# MODULO2_def.net
KiCad netlist of a schematic drawn in EAGLE
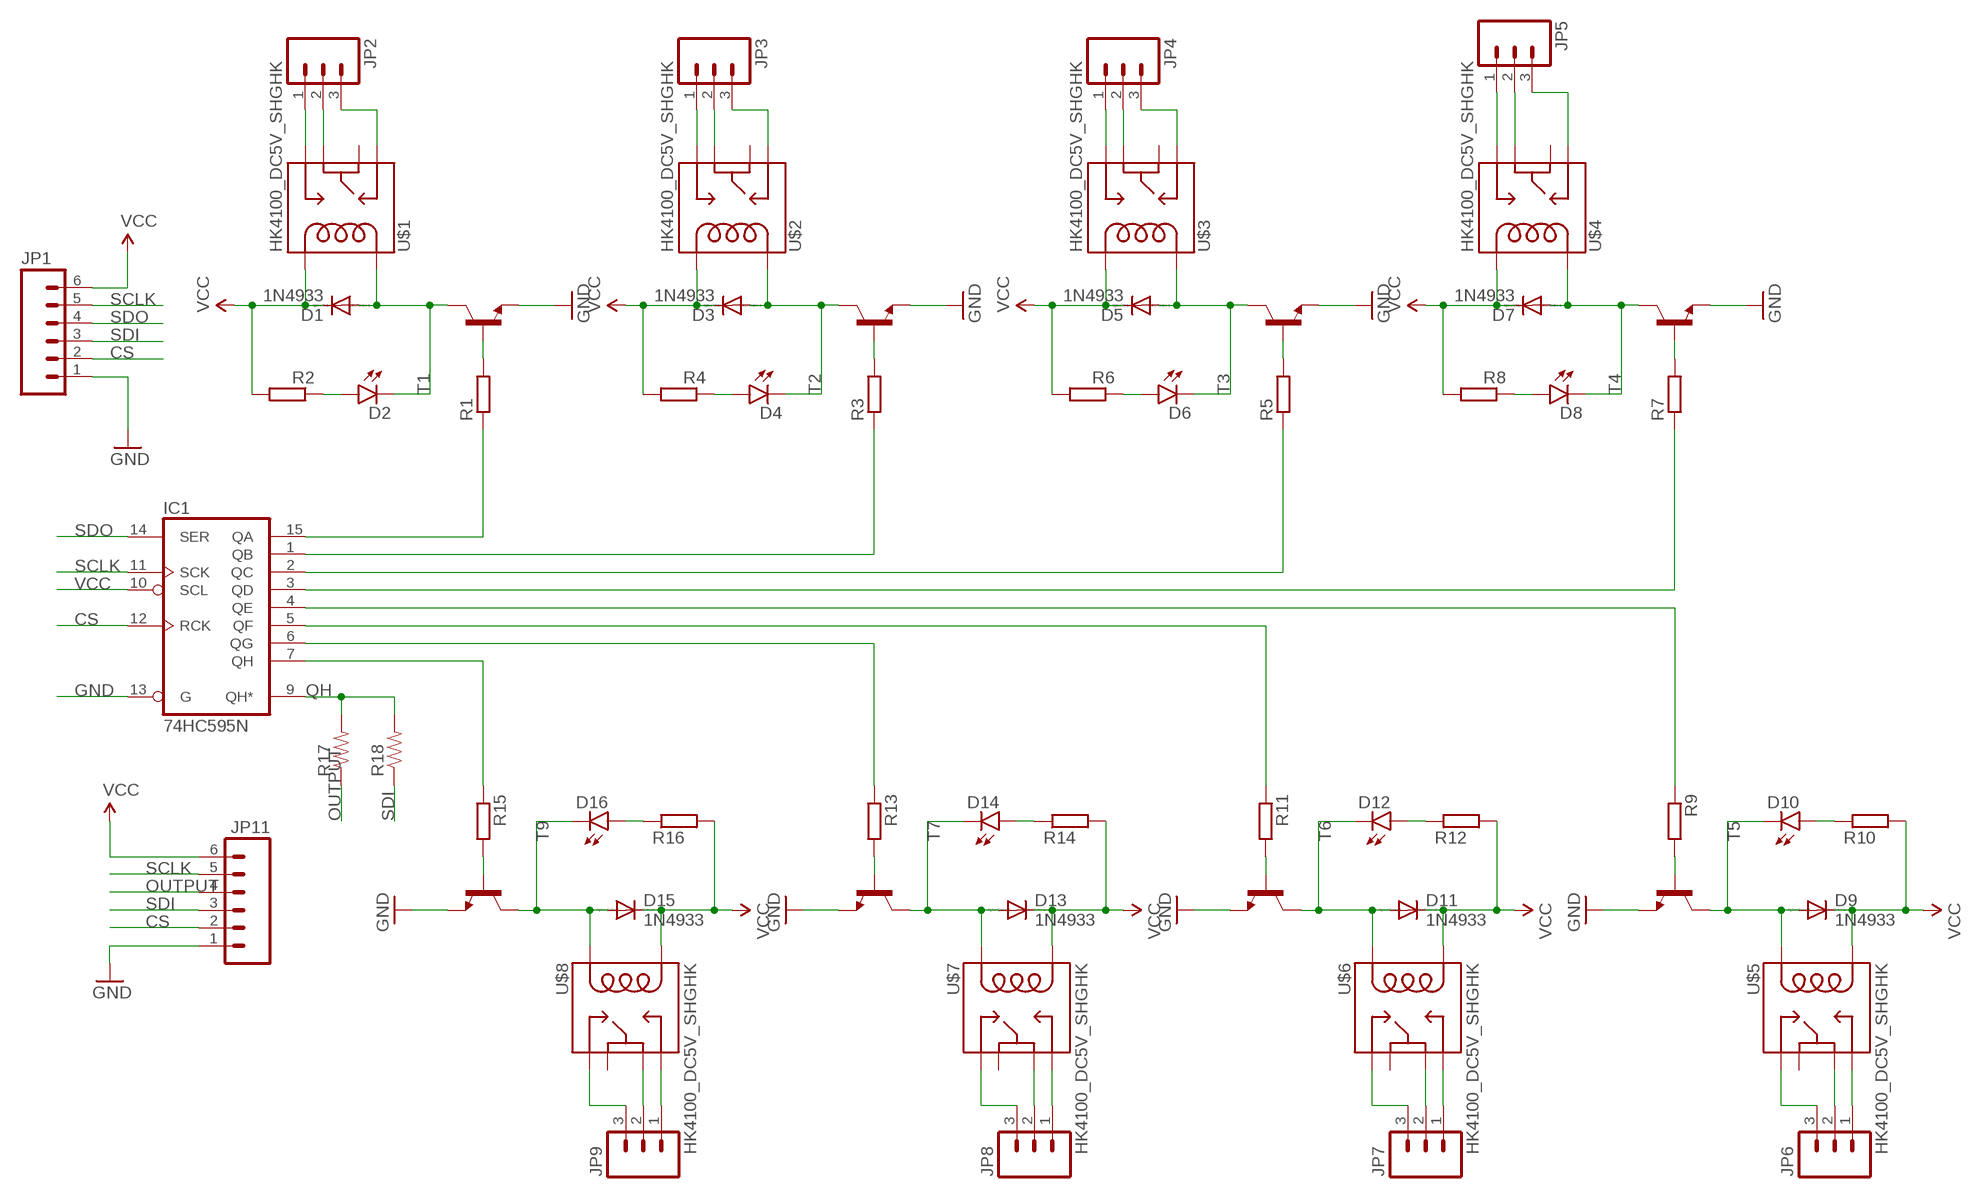
[diagram p0: schematic, sheet 1]

(export (version "E")
  (design (tool "Eeschema 10.0.6"))
  (components
    (comp (ref "D1")
      (value "1N4933")
      (footprint "eagle-import:DO41-10")
      (libsource (lib "eagle-import") (part "1N4933"))
    )
    (comp (ref "D2")
      (value "LED5MM")
      (footprint "eagle-import:LED5MM")
      (libsource (lib "eagle-import") (part "LED5MM"))
    )
    (comp (ref "D3")
      (value "1N4933")
      (footprint "eagle-import:DO41-10")
      (libsource (lib "eagle-import") (part "1N4933"))
    )
    (comp (ref "D4")
      (value "LED5MM")
      (footprint "eagle-import:LED5MM")
      (libsource (lib "eagle-import") (part "LED5MM"))
    )
    (comp (ref "D5")
      (value "1N4933")
      (footprint "eagle-import:DO41-10")
      (libsource (lib "eagle-import") (part "1N4933"))
    )
    (comp (ref "D6")
      (value "LED5MM")
      (footprint "eagle-import:LED5MM")
      (libsource (lib "eagle-import") (part "LED5MM"))
    )
    (comp (ref "D7")
      (value "1N4933")
      (footprint "eagle-import:DO41-10")
      (libsource (lib "eagle-import") (part "1N4933"))
    )
    (comp (ref "D8")
      (value "LED5MM")
      (footprint "eagle-import:LED5MM")
      (libsource (lib "eagle-import") (part "LED5MM"))
    )
    (comp (ref "D9")
      (value "1N4933")
      (footprint "eagle-import:DO41-10")
      (libsource (lib "eagle-import") (part "1N4933"))
    )
    (comp (ref "D10")
      (value "LED5MM")
      (footprint "eagle-import:LED5MM")
      (libsource (lib "eagle-import") (part "LED5MM"))
    )
    (comp (ref "D11")
      (value "1N4933")
      (footprint "eagle-import:DO41-10")
      (libsource (lib "eagle-import") (part "1N4933"))
    )
    (comp (ref "D12")
      (value "LED5MM")
      (footprint "eagle-import:LED5MM")
      (libsource (lib "eagle-import") (part "LED5MM"))
    )
    (comp (ref "D13")
      (value "1N4933")
      (footprint "eagle-import:DO41-10")
      (libsource (lib "eagle-import") (part "1N4933"))
    )
    (comp (ref "D14")
      (value "LED5MM")
      (footprint "eagle-import:LED5MM")
      (libsource (lib "eagle-import") (part "LED5MM"))
    )
    (comp (ref "D15")
      (value "1N4933")
      (footprint "eagle-import:DO41-10")
      (libsource (lib "eagle-import") (part "1N4933"))
    )
    (comp (ref "D16")
      (value "LED5MM")
      (footprint "eagle-import:LED5MM")
      (libsource (lib "eagle-import") (part "LED5MM"))
    )
    (comp (ref "IC1")
      (value "74HC595N")
      (footprint "eagle-import:DIL16")
      (libsource (lib "eagle-import") (part "74595NHC"))
    )
    (comp (ref "JP1")
      (value "M06LOCK")
      (footprint "eagle-import:1X06_LOCK")
      (libsource (lib "eagle-import") (part "M06LOCK"))
    )
    (comp (ref "JP2")
      (value "M03-SCREW-5MM")
      (footprint "eagle-import:SCREWTERMINAL-5MM-3")
      (libsource (lib "eagle-import") (part "M03-SCREW-5MM"))
    )
    (comp (ref "JP3")
      (value "M03-SCREW-5MM")
      (footprint "eagle-import:SCREWTERMINAL-5MM-3")
      (libsource (lib "eagle-import") (part "M03-SCREW-5MM"))
    )
    (comp (ref "JP4")
      (value "M03-SCREW-5MM")
      (footprint "eagle-import:SCREWTERMINAL-5MM-3")
      (libsource (lib "eagle-import") (part "M03-SCREW-5MM"))
    )
    (comp (ref "JP5")
      (value "M03-SCREW-5MM")
      (footprint "eagle-import:SCREWTERMINAL-5MM-3")
      (libsource (lib "eagle-import") (part "M03-SCREW-5MM"))
    )
    (comp (ref "JP6")
      (value "M03-SCREW-5MM")
      (footprint "eagle-import:SCREWTERMINAL-5MM-3")
      (libsource (lib "eagle-import") (part "M03-SCREW-5MM"))
    )
    (comp (ref "JP7")
      (value "M03-SCREW-5MM")
      (footprint "eagle-import:SCREWTERMINAL-5MM-3")
      (libsource (lib "eagle-import") (part "M03-SCREW-5MM"))
    )
    (comp (ref "JP8")
      (value "M03-SCREW-5MM")
      (footprint "eagle-import:SCREWTERMINAL-5MM-3")
      (libsource (lib "eagle-import") (part "M03-SCREW-5MM"))
    )
    (comp (ref "JP9")
      (value "M03-SCREW-5MM")
      (footprint "eagle-import:SCREWTERMINAL-5MM-3")
      (libsource (lib "eagle-import") (part "M03-SCREW-5MM"))
    )
    (comp (ref "JP11")
      (value "M06LOCK")
      (footprint "eagle-import:1X06_LOCK")
      (libsource (lib "eagle-import") (part "M06LOCK"))
    )
    (comp (ref "R1")
      (value "R-EU_R0805")
      (footprint "eagle-import:R0805")
      (libsource (lib "eagle-import") (part "R-EU_R0805"))
    )
    (comp (ref "R2")
      (value "R-EU_R0805")
      (footprint "eagle-import:R0805")
      (libsource (lib "eagle-import") (part "R-EU_R0805"))
    )
    (comp (ref "R3")
      (value "R-EU_R0805")
      (footprint "eagle-import:R0805")
      (libsource (lib "eagle-import") (part "R-EU_R0805"))
    )
    (comp (ref "R4")
      (value "R-EU_R0805")
      (footprint "eagle-import:R0805")
      (libsource (lib "eagle-import") (part "R-EU_R0805"))
    )
    (comp (ref "R5")
      (value "R-EU_R0805")
      (footprint "eagle-import:R0805")
      (libsource (lib "eagle-import") (part "R-EU_R0805"))
    )
    (comp (ref "R6")
      (value "R-EU_R0805")
      (footprint "eagle-import:R0805")
      (libsource (lib "eagle-import") (part "R-EU_R0805"))
    )
    (comp (ref "R7")
      (value "R-EU_R0805")
      (footprint "eagle-import:R0805")
      (libsource (lib "eagle-import") (part "R-EU_R0805"))
    )
    (comp (ref "R8")
      (value "R-EU_R0805")
      (footprint "eagle-import:R0805")
      (libsource (lib "eagle-import") (part "R-EU_R0805"))
    )
    (comp (ref "R9")
      (value "R-EU_R0805")
      (footprint "eagle-import:R0805")
      (libsource (lib "eagle-import") (part "R-EU_R0805"))
    )
    (comp (ref "R10")
      (value "R-EU_R0805")
      (footprint "eagle-import:R0805")
      (libsource (lib "eagle-import") (part "R-EU_R0805"))
    )
    (comp (ref "R11")
      (value "R-EU_R0805")
      (footprint "eagle-import:R0805")
      (libsource (lib "eagle-import") (part "R-EU_R0805"))
    )
    (comp (ref "R12")
      (value "R-EU_R0805")
      (footprint "eagle-import:R0805")
      (libsource (lib "eagle-import") (part "R-EU_R0805"))
    )
    (comp (ref "R13")
      (value "R-EU_R0805")
      (footprint "eagle-import:R0805")
      (libsource (lib "eagle-import") (part "R-EU_R0805"))
    )
    (comp (ref "R14")
      (value "R-EU_R0805")
      (footprint "eagle-import:R0805")
      (libsource (lib "eagle-import") (part "R-EU_R0805"))
    )
    (comp (ref "R15")
      (value "R-EU_R0805")
      (footprint "eagle-import:R0805")
      (libsource (lib "eagle-import") (part "R-EU_R0805"))
    )
    (comp (ref "R16")
      (value "R-EU_R0805")
      (footprint "eagle-import:R0805")
      (libsource (lib "eagle-import") (part "R-EU_R0805"))
    )
    (comp (ref "R17")
      (value "RESISTOR0805-RES")
      (footprint "eagle-import:0805")
      (libsource (lib "eagle-import") (part "RESISTOR0805-RES"))
    )
    (comp (ref "R18")
      (value "RESISTOR0805-RES")
      (footprint "eagle-import:0805")
      (libsource (lib "eagle-import") (part "RESISTOR0805-RES"))
    )
    (comp (ref "T1")
      (value "-NPN-TO92-EBC")
      (footprint "eagle-import:TO92-EBC")
      (libsource (lib "eagle-import") (part "-NPN-TO92-EBC"))
    )
    (comp (ref "T2")
      (value "-NPN-TO92-EBC")
      (footprint "eagle-import:TO92-EBC")
      (libsource (lib "eagle-import") (part "-NPN-TO92-EBC"))
    )
    (comp (ref "T3")
      (value "-NPN-TO92-EBC")
      (footprint "eagle-import:TO92-EBC")
      (libsource (lib "eagle-import") (part "-NPN-TO92-EBC"))
    )
    (comp (ref "T4")
      (value "-NPN-TO92-EBC")
      (footprint "eagle-import:TO92-EBC")
      (libsource (lib "eagle-import") (part "-NPN-TO92-EBC"))
    )
    (comp (ref "T5")
      (value "-NPN-TO92-EBC")
      (footprint "eagle-import:TO92-EBC")
      (libsource (lib "eagle-import") (part "-NPN-TO92-EBC"))
    )
    (comp (ref "T6")
      (value "-NPN-TO92-EBC")
      (footprint "eagle-import:TO92-EBC")
      (libsource (lib "eagle-import") (part "-NPN-TO92-EBC"))
    )
    (comp (ref "T7")
      (value "-NPN-TO92-EBC")
      (footprint "eagle-import:TO92-EBC")
      (libsource (lib "eagle-import") (part "-NPN-TO92-EBC"))
    )
    (comp (ref "T9")
      (value "-NPN-TO92-EBC")
      (footprint "eagle-import:TO92-EBC")
      (libsource (lib "eagle-import") (part "-NPN-TO92-EBC"))
    )
    (comp (ref "U$1")
      (value "HK4100_DC5V_SHGHK")
      (footprint "eagle-import:HK4100")
      (libsource (lib "eagle-import") (part "HK4100_DC5V_SHGHK"))
    )
    (comp (ref "U$2")
      (value "HK4100_DC5V_SHGHK")
      (footprint "eagle-import:HK4100")
      (libsource (lib "eagle-import") (part "HK4100_DC5V_SHGHK"))
    )
    (comp (ref "U$3")
      (value "HK4100_DC5V_SHGHK")
      (footprint "eagle-import:HK4100")
      (libsource (lib "eagle-import") (part "HK4100_DC5V_SHGHK"))
    )
    (comp (ref "U$4")
      (value "HK4100_DC5V_SHGHK")
      (footprint "eagle-import:HK4100")
      (libsource (lib "eagle-import") (part "HK4100_DC5V_SHGHK"))
    )
    (comp (ref "U$5")
      (value "HK4100_DC5V_SHGHK")
      (footprint "eagle-import:HK4100")
      (libsource (lib "eagle-import") (part "HK4100_DC5V_SHGHK"))
    )
    (comp (ref "U$6")
      (value "HK4100_DC5V_SHGHK")
      (footprint "eagle-import:HK4100")
      (libsource (lib "eagle-import") (part "HK4100_DC5V_SHGHK"))
    )
    (comp (ref "U$7")
      (value "HK4100_DC5V_SHGHK")
      (footprint "eagle-import:HK4100")
      (libsource (lib "eagle-import") (part "HK4100_DC5V_SHGHK"))
    )
    (comp (ref "U$8")
      (value "HK4100_DC5V_SHGHK")
      (footprint "eagle-import:HK4100")
      (libsource (lib "eagle-import") (part "HK4100_DC5V_SHGHK"))
    )
  )
  (nets
    (net (code "1") (name "/CS") (class "Default")
      (node (ref "IC1") (pin "12") (pinfunction "RCK_12") (pintype "input"))
      (node (ref "JP1") (pin "2") (pinfunction "2_2") (pintype "passive"))
      (node (ref "JP11") (pin "2") (pinfunction "2_2") (pintype "passive"))
    )
    (net (code "2") (name "/OUTPUT") (class "Default")
      (node (ref "JP11") (pin "4") (pinfunction "4_4") (pintype "passive"))
      (node (ref "R17") (pin "1") (pinfunction "1_1") (pintype "passive"))
    )
    (net (code "3") (name "/QH") (class "Default")
      (node (ref "IC1") (pin "9") (pinfunction "QH*_9") (pintype "tri_state"))
      (node (ref "R17") (pin "2") (pinfunction "2_2") (pintype "passive"))
      (node (ref "R18") (pin "2") (pinfunction "2_2") (pintype "passive"))
    )
    (net (code "4") (name "/SCLK") (class "Default")
      (node (ref "IC1") (pin "11") (pinfunction "SCK_11") (pintype "input"))
      (node (ref "JP1") (pin "5") (pinfunction "5_5") (pintype "passive"))
      (node (ref "JP11") (pin "5") (pinfunction "5_5") (pintype "passive"))
    )
    (net (code "5") (name "/SDI") (class "Default")
      (node (ref "JP1") (pin "3") (pinfunction "3_3") (pintype "passive"))
      (node (ref "JP11") (pin "3") (pinfunction "3_3") (pintype "passive"))
      (node (ref "R18") (pin "1") (pinfunction "1_1") (pintype "passive"))
    )
    (net (code "6") (name "/SDO") (class "Default")
      (node (ref "IC1") (pin "14") (pinfunction "SER_14") (pintype "input"))
      (node (ref "JP1") (pin "4") (pinfunction "4_4") (pintype "passive"))
    )
    (net (code "7") (name "GND") (class "Default")
      (node (ref "IC1") (pin "13") (pinfunction "G_13") (pintype "input"))
      (node (ref "JP1") (pin "1") (pinfunction "1_1") (pintype "passive"))
      (node (ref "JP11") (pin "1") (pinfunction "1_1") (pintype "passive"))
      (node (ref "T1") (pin "E") (pinfunction "E_E") (pintype "passive"))
      (node (ref "T2") (pin "E") (pinfunction "E_E") (pintype "passive"))
      (node (ref "T3") (pin "E") (pinfunction "E_E") (pintype "passive"))
      (node (ref "T4") (pin "E") (pinfunction "E_E") (pintype "passive"))
      (node (ref "T5") (pin "E") (pinfunction "E_E") (pintype "passive"))
      (node (ref "T6") (pin "E") (pinfunction "E_E") (pintype "passive"))
      (node (ref "T7") (pin "E") (pinfunction "E_E") (pintype "passive"))
      (node (ref "T9") (pin "E") (pinfunction "E_E") (pintype "passive"))
    )
    (net (code "8") (name "Net-(D2-C)") (class "Default")
      (node (ref "D1") (pin "A") (pinfunction "A_A") (pintype "passive"))
      (node (ref "D2") (pin "K") (pinfunction "C_K") (pintype "passive"))
      (node (ref "T1") (pin "C") (pinfunction "C_C") (pintype "passive"))
      (node (ref "U$1") (pin "6") (pinfunction "2_6") (pintype "bidirectional"))
    )
    (net (code "9") (name "Net-(D2-PadA)") (class "Default")
      (node (ref "D2") (pin "A") (pinfunction "A_A") (pintype "passive"))
      (node (ref "R2") (pin "1") (pinfunction "1_1") (pintype "passive"))
    )
    (net (code "10") (name "Net-(D4-C)") (class "Default")
      (node (ref "D3") (pin "A") (pinfunction "A_A") (pintype "passive"))
      (node (ref "D4") (pin "K") (pinfunction "C_K") (pintype "passive"))
      (node (ref "T2") (pin "C") (pinfunction "C_C") (pintype "passive"))
      (node (ref "U$2") (pin "6") (pinfunction "2_6") (pintype "bidirectional"))
    )
    (net (code "11") (name "Net-(D4-PadA)") (class "Default")
      (node (ref "D4") (pin "A") (pinfunction "A_A") (pintype "passive"))
      (node (ref "R4") (pin "1") (pinfunction "1_1") (pintype "passive"))
    )
    (net (code "12") (name "Net-(D6-C)") (class "Default")
      (node (ref "D5") (pin "A") (pinfunction "A_A") (pintype "passive"))
      (node (ref "D6") (pin "K") (pinfunction "C_K") (pintype "passive"))
      (node (ref "T3") (pin "C") (pinfunction "C_C") (pintype "passive"))
      (node (ref "U$3") (pin "6") (pinfunction "2_6") (pintype "bidirectional"))
    )
    (net (code "13") (name "Net-(D6-PadA)") (class "Default")
      (node (ref "D6") (pin "A") (pinfunction "A_A") (pintype "passive"))
      (node (ref "R6") (pin "1") (pinfunction "1_1") (pintype "passive"))
    )
    (net (code "14") (name "Net-(D8-C)") (class "Default")
      (node (ref "D7") (pin "A") (pinfunction "A_A") (pintype "passive"))
      (node (ref "D8") (pin "K") (pinfunction "C_K") (pintype "passive"))
      (node (ref "T4") (pin "C") (pinfunction "C_C") (pintype "passive"))
      (node (ref "U$4") (pin "6") (pinfunction "2_6") (pintype "bidirectional"))
    )
    (net (code "15") (name "Net-(D8-PadA)") (class "Default")
      (node (ref "D8") (pin "A") (pinfunction "A_A") (pintype "passive"))
      (node (ref "R8") (pin "1") (pinfunction "1_1") (pintype "passive"))
    )
    (net (code "16") (name "Net-(D10-C)") (class "Default")
      (node (ref "D10") (pin "K") (pinfunction "C_K") (pintype "passive"))
      (node (ref "D9") (pin "A") (pinfunction "A_A") (pintype "passive"))
      (node (ref "T5") (pin "C") (pinfunction "C_C") (pintype "passive"))
      (node (ref "U$5") (pin "6") (pinfunction "2_6") (pintype "bidirectional"))
    )
    (net (code "17") (name "Net-(D10-PadA)") (class "Default")
      (node (ref "D10") (pin "A") (pinfunction "A_A") (pintype "passive"))
      (node (ref "R10") (pin "1") (pinfunction "1_1") (pintype "passive"))
    )
    (net (code "18") (name "Net-(D12-C)") (class "Default")
      (node (ref "D11") (pin "A") (pinfunction "A_A") (pintype "passive"))
      (node (ref "D12") (pin "K") (pinfunction "C_K") (pintype "passive"))
      (node (ref "T6") (pin "C") (pinfunction "C_C") (pintype "passive"))
      (node (ref "U$6") (pin "6") (pinfunction "2_6") (pintype "bidirectional"))
    )
    (net (code "19") (name "Net-(D12-PadA)") (class "Default")
      (node (ref "D12") (pin "A") (pinfunction "A_A") (pintype "passive"))
      (node (ref "R12") (pin "1") (pinfunction "1_1") (pintype "passive"))
    )
    (net (code "20") (name "Net-(D14-C)") (class "Default")
      (node (ref "D13") (pin "A") (pinfunction "A_A") (pintype "passive"))
      (node (ref "D14") (pin "K") (pinfunction "C_K") (pintype "passive"))
      (node (ref "T7") (pin "C") (pinfunction "C_C") (pintype "passive"))
      (node (ref "U$7") (pin "6") (pinfunction "2_6") (pintype "bidirectional"))
    )
    (net (code "21") (name "Net-(D14-PadA)") (class "Default")
      (node (ref "D14") (pin "A") (pinfunction "A_A") (pintype "passive"))
      (node (ref "R14") (pin "1") (pinfunction "1_1") (pintype "passive"))
    )
    (net (code "22") (name "Net-(D16-C)") (class "Default")
      (node (ref "D15") (pin "A") (pinfunction "A_A") (pintype "passive"))
      (node (ref "D16") (pin "K") (pinfunction "C_K") (pintype "passive"))
      (node (ref "T9") (pin "C") (pinfunction "C_C") (pintype "passive"))
      (node (ref "U$8") (pin "6") (pinfunction "2_6") (pintype "bidirectional"))
    )
    (net (code "23") (name "Net-(D16-PadA)") (class "Default")
      (node (ref "D16") (pin "A") (pinfunction "A_A") (pintype "passive"))
      (node (ref "R16") (pin "1") (pinfunction "1_1") (pintype "passive"))
    )
    (net (code "24") (name "Net-(IC1A-QA)") (class "Default")
      (node (ref "IC1") (pin "15") (pinfunction "QA_15") (pintype "tri_state"))
      (node (ref "R1") (pin "1") (pinfunction "1_1") (pintype "passive"))
    )
    (net (code "25") (name "Net-(IC1A-QB)") (class "Default")
      (node (ref "IC1") (pin "1") (pinfunction "QB_1") (pintype "tri_state"))
      (node (ref "R3") (pin "1") (pinfunction "1_1") (pintype "passive"))
    )
    (net (code "26") (name "Net-(IC1A-QC)") (class "Default")
      (node (ref "IC1") (pin "2") (pinfunction "QC_2") (pintype "tri_state"))
      (node (ref "R5") (pin "1") (pinfunction "1_1") (pintype "passive"))
    )
    (net (code "27") (name "Net-(IC1A-QD)") (class "Default")
      (node (ref "IC1") (pin "3") (pinfunction "QD_3") (pintype "tri_state"))
      (node (ref "R7") (pin "1") (pinfunction "1_1") (pintype "passive"))
    )
    (net (code "28") (name "Net-(IC1A-QE)") (class "Default")
      (node (ref "IC1") (pin "4") (pinfunction "QE_4") (pintype "tri_state"))
      (node (ref "R9") (pin "1") (pinfunction "1_1") (pintype "passive"))
    )
    (net (code "29") (name "Net-(IC1A-QF)") (class "Default")
      (node (ref "IC1") (pin "5") (pinfunction "QF_5") (pintype "tri_state"))
      (node (ref "R11") (pin "1") (pinfunction "1_1") (pintype "passive"))
    )
    (net (code "30") (name "Net-(IC1A-QG)") (class "Default")
      (node (ref "IC1") (pin "6") (pinfunction "QG_6") (pintype "tri_state"))
      (node (ref "R13") (pin "1") (pinfunction "1_1") (pintype "passive"))
    )
    (net (code "31") (name "Net-(IC1A-QH)") (class "Default")
      (node (ref "IC1") (pin "7") (pinfunction "QH_7") (pintype "tri_state"))
      (node (ref "R15") (pin "1") (pinfunction "1_1") (pintype "passive"))
    )
    (net (code "32") (name "Net-(R1-Pad2)") (class "Default")
      (node (ref "R1") (pin "2") (pinfunction "2_2") (pintype "passive"))
      (node (ref "T1") (pin "B") (pinfunction "B_B") (pintype "passive"))
    )
    (net (code "33") (name "Net-(R3-Pad2)") (class "Default")
      (node (ref "R3") (pin "2") (pinfunction "2_2") (pintype "passive"))
      (node (ref "T2") (pin "B") (pinfunction "B_B") (pintype "passive"))
    )
    (net (code "34") (name "Net-(R5-Pad2)") (class "Default")
      (node (ref "R5") (pin "2") (pinfunction "2_2") (pintype "passive"))
      (node (ref "T3") (pin "B") (pinfunction "B_B") (pintype "passive"))
    )
    (net (code "35") (name "Net-(R7-Pad2)") (class "Default")
      (node (ref "R7") (pin "2") (pinfunction "2_2") (pintype "passive"))
      (node (ref "T4") (pin "B") (pinfunction "B_B") (pintype "passive"))
    )
    (net (code "36") (name "Net-(R9-Pad2)") (class "Default")
      (node (ref "R9") (pin "2") (pinfunction "2_2") (pintype "passive"))
      (node (ref "T5") (pin "B") (pinfunction "B_B") (pintype "passive"))
    )
    (net (code "37") (name "Net-(R11-Pad2)") (class "Default")
      (node (ref "R11") (pin "2") (pinfunction "2_2") (pintype "passive"))
      (node (ref "T6") (pin "B") (pinfunction "B_B") (pintype "passive"))
    )
    (net (code "38") (name "Net-(R13-Pad2)") (class "Default")
      (node (ref "R13") (pin "2") (pinfunction "2_2") (pintype "passive"))
      (node (ref "T7") (pin "B") (pinfunction "B_B") (pintype "passive"))
    )
    (net (code "39") (name "Net-(R15-Pad2)") (class "Default")
      (node (ref "R15") (pin "2") (pinfunction "2_2") (pintype "passive"))
      (node (ref "T9") (pin "B") (pinfunction "B_B") (pintype "passive"))
    )
    (net (code "40") (name "Net-(U$1-1)") (class "Default")
      (node (ref "JP2") (pin "3") (pinfunction "3_3") (pintype "passive"))
      (node (ref "U$1") (pin "7") (pinfunction "1_7") (pintype "bidirectional"))
    )
    (net (code "41") (name "Net-(U$1-6)") (class "Default")
      (node (ref "JP2") (pin "2") (pinfunction "2_2") (pintype "passive"))
      (node (ref "U$1") (pin "14") (pinfunction "6_14") (pintype "bidirectional"))
    )
    (net (code "42") (name "Net-(U$1-10)") (class "Default")
      (node (ref "JP2") (pin "1") (pinfunction "1_1") (pintype "passive"))
      (node (ref "U$1") (pin "8") (pinfunction "10_8") (pintype "bidirectional"))
    )
    (net (code "43") (name "Net-(U$2-1)") (class "Default")
      (node (ref "JP3") (pin "3") (pinfunction "3_3") (pintype "passive"))
      (node (ref "U$2") (pin "7") (pinfunction "1_7") (pintype "bidirectional"))
    )
    (net (code "44") (name "Net-(U$2-6)") (class "Default")
      (node (ref "JP3") (pin "2") (pinfunction "2_2") (pintype "passive"))
      (node (ref "U$2") (pin "14") (pinfunction "6_14") (pintype "bidirectional"))
    )
    (net (code "45") (name "Net-(U$2-10)") (class "Default")
      (node (ref "JP3") (pin "1") (pinfunction "1_1") (pintype "passive"))
      (node (ref "U$2") (pin "8") (pinfunction "10_8") (pintype "bidirectional"))
    )
    (net (code "46") (name "Net-(U$3-1)") (class "Default")
      (node (ref "JP4") (pin "3") (pinfunction "3_3") (pintype "passive"))
      (node (ref "U$3") (pin "7") (pinfunction "1_7") (pintype "bidirectional"))
    )
    (net (code "47") (name "Net-(U$3-6)") (class "Default")
      (node (ref "JP4") (pin "2") (pinfunction "2_2") (pintype "passive"))
      (node (ref "U$3") (pin "14") (pinfunction "6_14") (pintype "bidirectional"))
    )
    (net (code "48") (name "Net-(U$3-10)") (class "Default")
      (node (ref "JP4") (pin "1") (pinfunction "1_1") (pintype "passive"))
      (node (ref "U$3") (pin "8") (pinfunction "10_8") (pintype "bidirectional"))
    )
    (net (code "49") (name "Net-(U$4-1)") (class "Default")
      (node (ref "JP5") (pin "3") (pinfunction "3_3") (pintype "passive"))
      (node (ref "U$4") (pin "7") (pinfunction "1_7") (pintype "bidirectional"))
    )
    (net (code "50") (name "Net-(U$4-6)") (class "Default")
      (node (ref "JP5") (pin "2") (pinfunction "2_2") (pintype "passive"))
      (node (ref "U$4") (pin "14") (pinfunction "6_14") (pintype "bidirectional"))
    )
    (net (code "51") (name "Net-(U$4-10)") (class "Default")
      (node (ref "JP5") (pin "1") (pinfunction "1_1") (pintype "passive"))
      (node (ref "U$4") (pin "8") (pinfunction "10_8") (pintype "bidirectional"))
    )
    (net (code "52") (name "Net-(U$5-1)") (class "Default")
      (node (ref "JP6") (pin "3") (pinfunction "3_3") (pintype "passive"))
      (node (ref "U$5") (pin "7") (pinfunction "1_7") (pintype "bidirectional"))
    )
    (net (code "53") (name "Net-(U$5-6)") (class "Default")
      (node (ref "JP6") (pin "2") (pinfunction "2_2") (pintype "passive"))
      (node (ref "U$5") (pin "14") (pinfunction "6_14") (pintype "bidirectional"))
    )
    (net (code "54") (name "Net-(U$5-10)") (class "Default")
      (node (ref "JP6") (pin "1") (pinfunction "1_1") (pintype "passive"))
      (node (ref "U$5") (pin "8") (pinfunction "10_8") (pintype "bidirectional"))
    )
    (net (code "55") (name "Net-(U$6-1)") (class "Default")
      (node (ref "JP7") (pin "3") (pinfunction "3_3") (pintype "passive"))
      (node (ref "U$6") (pin "7") (pinfunction "1_7") (pintype "bidirectional"))
    )
    (net (code "56") (name "Net-(U$6-6)") (class "Default")
      (node (ref "JP7") (pin "2") (pinfunction "2_2") (pintype "passive"))
      (node (ref "U$6") (pin "14") (pinfunction "6_14") (pintype "bidirectional"))
    )
    (net (code "57") (name "Net-(U$6-10)") (class "Default")
      (node (ref "JP7") (pin "1") (pinfunction "1_1") (pintype "passive"))
      (node (ref "U$6") (pin "8") (pinfunction "10_8") (pintype "bidirectional"))
    )
    (net (code "58") (name "Net-(U$7-1)") (class "Default")
      (node (ref "JP8") (pin "3") (pinfunction "3_3") (pintype "passive"))
      (node (ref "U$7") (pin "7") (pinfunction "1_7") (pintype "bidirectional"))
    )
    (net (code "59") (name "Net-(U$7-6)") (class "Default")
      (node (ref "JP8") (pin "2") (pinfunction "2_2") (pintype "passive"))
      (node (ref "U$7") (pin "14") (pinfunction "6_14") (pintype "bidirectional"))
    )
    (net (code "60") (name "Net-(U$7-10)") (class "Default")
      (node (ref "JP8") (pin "1") (pinfunction "1_1") (pintype "passive"))
      (node (ref "U$7") (pin "8") (pinfunction "10_8") (pintype "bidirectional"))
    )
    (net (code "61") (name "Net-(U$8-1)") (class "Default")
      (node (ref "JP9") (pin "3") (pinfunction "3_3") (pintype "passive"))
      (node (ref "U$8") (pin "7") (pinfunction "1_7") (pintype "bidirectional"))
    )
    (net (code "62") (name "Net-(U$8-6)") (class "Default")
      (node (ref "JP9") (pin "2") (pinfunction "2_2") (pintype "passive"))
      (node (ref "U$8") (pin "14") (pinfunction "6_14") (pintype "bidirectional"))
    )
    (net (code "63") (name "Net-(U$8-10)") (class "Default")
      (node (ref "JP9") (pin "1") (pinfunction "1_1") (pintype "passive"))
      (node (ref "U$8") (pin "8") (pinfunction "10_8") (pintype "bidirectional"))
    )
    (net (code "64") (name "VCC") (class "Default")
      (node (ref "D1") (pin "C") (pinfunction "C_C") (pintype "passive"))
      (node (ref "D11") (pin "C") (pinfunction "C_C") (pintype "passive"))
      (node (ref "D13") (pin "C") (pinfunction "C_C") (pintype "passive"))
      (node (ref "D15") (pin "C") (pinfunction "C_C") (pintype "passive"))
      (node (ref "D3") (pin "C") (pinfunction "C_C") (pintype "passive"))
      (node (ref "D5") (pin "C") (pinfunction "C_C") (pintype "passive"))
      (node (ref "D7") (pin "C") (pinfunction "C_C") (pintype "passive"))
      (node (ref "D9") (pin "C") (pinfunction "C_C") (pintype "passive"))
      (node (ref "IC1") (pin "10") (pinfunction "SCL_10") (pintype "input"))
      (node (ref "JP1") (pin "6") (pinfunction "6_6") (pintype "passive"))
      (node (ref "JP11") (pin "6") (pinfunction "6_6") (pintype "passive"))
      (node (ref "R10") (pin "2") (pinfunction "2_2") (pintype "passive"))
      (node (ref "R12") (pin "2") (pinfunction "2_2") (pintype "passive"))
      (node (ref "R14") (pin "2") (pinfunction "2_2") (pintype "passive"))
      (node (ref "R16") (pin "2") (pinfunction "2_2") (pintype "passive"))
      (node (ref "R2") (pin "2") (pinfunction "2_2") (pintype "passive"))
      (node (ref "R4") (pin "2") (pinfunction "2_2") (pintype "passive"))
      (node (ref "R6") (pin "2") (pinfunction "2_2") (pintype "passive"))
      (node (ref "R8") (pin "2") (pinfunction "2_2") (pintype "passive"))
      (node (ref "U$1") (pin "9") (pinfunction "9_9") (pintype "bidirectional"))
      (node (ref "U$2") (pin "9") (pinfunction "9_9") (pintype "bidirectional"))
      (node (ref "U$3") (pin "9") (pinfunction "9_9") (pintype "bidirectional"))
      (node (ref "U$4") (pin "9") (pinfunction "9_9") (pintype "bidirectional"))
      (node (ref "U$5") (pin "9") (pinfunction "9_9") (pintype "bidirectional"))
      (node (ref "U$6") (pin "9") (pinfunction "9_9") (pintype "bidirectional"))
      (node (ref "U$7") (pin "9") (pinfunction "9_9") (pintype "bidirectional"))
      (node (ref "U$8") (pin "9") (pinfunction "9_9") (pintype "bidirectional"))
    )
    (net (code "65") (name "unconnected-(U$1-5-Pad1)") (class "Default")
      (node (ref "U$1") (pin "1") (pinfunction "5_1") (pintype "bidirectional"))
    )
    (net (code "66") (name "unconnected-(U$2-5-Pad1)") (class "Default")
      (node (ref "U$2") (pin "1") (pinfunction "5_1") (pintype "bidirectional"))
    )
    (net (code "67") (name "unconnected-(U$3-5-Pad1)") (class "Default")
      (node (ref "U$3") (pin "1") (pinfunction "5_1") (pintype "bidirectional"))
    )
    (net (code "68") (name "unconnected-(U$4-5-Pad1)") (class "Default")
      (node (ref "U$4") (pin "1") (pinfunction "5_1") (pintype "bidirectional"))
    )
    (net (code "69") (name "unconnected-(U$5-5-Pad1)") (class "Default")
      (node (ref "U$5") (pin "1") (pinfunction "5_1") (pintype "bidirectional"))
    )
    (net (code "70") (name "unconnected-(U$6-5-Pad1)") (class "Default")
      (node (ref "U$6") (pin "1") (pinfunction "5_1") (pintype "bidirectional"))
    )
    (net (code "71") (name "unconnected-(U$7-5-Pad1)") (class "Default")
      (node (ref "U$7") (pin "1") (pinfunction "5_1") (pintype "bidirectional"))
    )
    (net (code "72") (name "unconnected-(U$8-5-Pad1)") (class "Default")
      (node (ref "U$8") (pin "1") (pinfunction "5_1") (pintype "bidirectional"))
    )
  )
)
